# controlshield.net
KiCad netlist of a schematic drawn in EAGLE
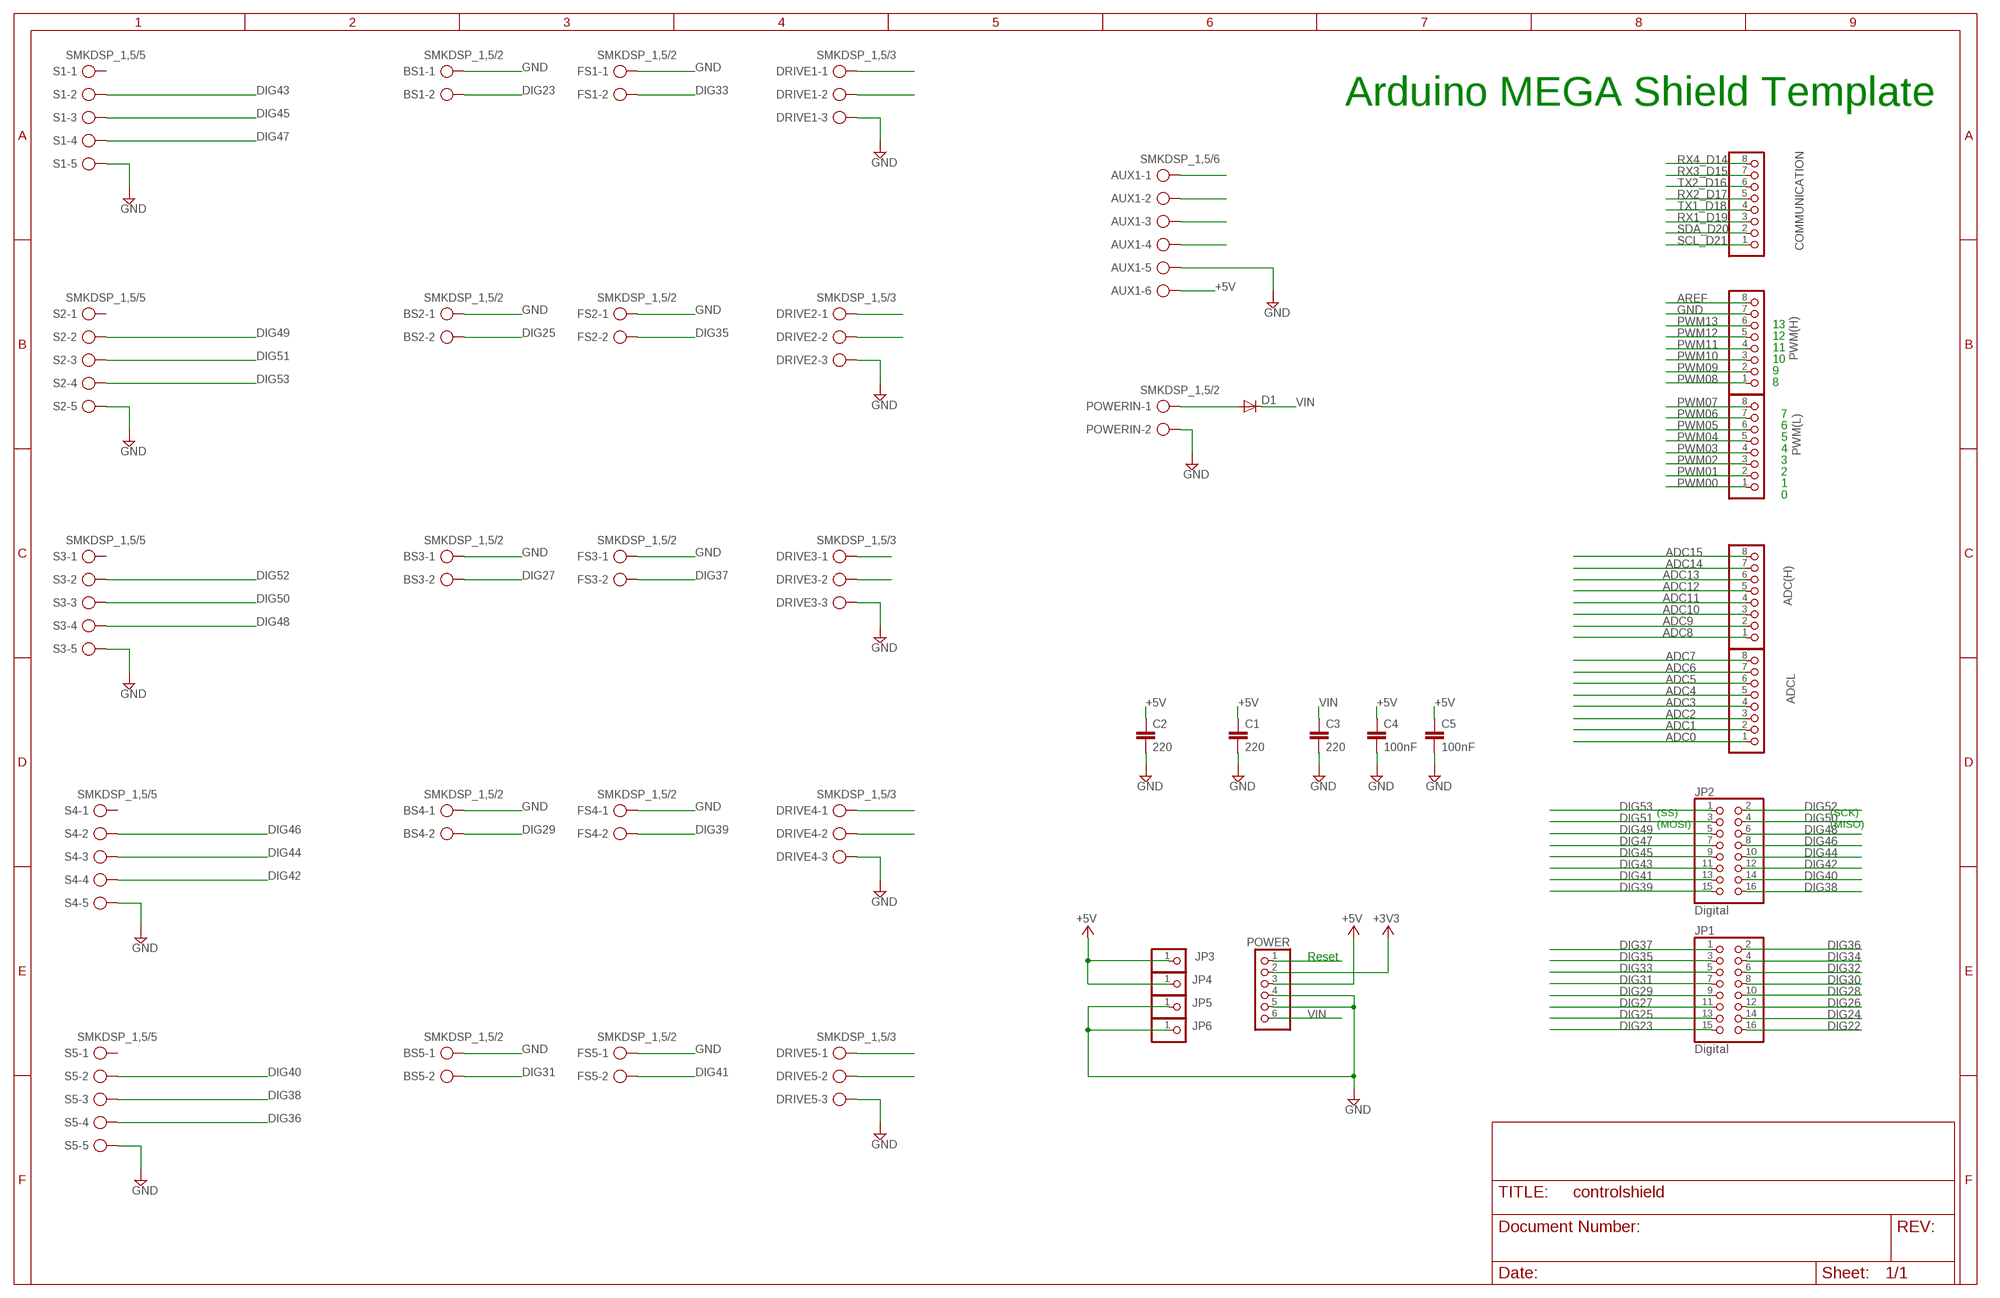
[diagram p0: schematic, sheet 1]

(export (version "E")
  (design (tool "Eeschema 10.0.6"))
  (components
    (comp (ref "ADC(H)")
      (value "PINHD-1X8")
      (footprint "eagle-import:1X08")
      (libsource (lib "eagle-import") (part "PINHD-1X8"))
    )
    (comp (ref "ADCL")
      (value "PINHD-1X8")
      (footprint "eagle-import:1X08")
      (libsource (lib "eagle-import") (part "PINHD-1X8"))
    )
    (comp (ref "AUX1")
      (value "SMKDSP_1,5/6")
      (footprint "eagle-import:SMKDSP_1,5_6")
      (fields (field (name "MF") "FARNELL") (field (name "MPN") "1733619"))
      (libsource (lib "eagle-import") (part "SMKDSP_1,5/6"))
    )
    (comp (ref "BS1")
      (value "SMKDSP_1,5/2")
      (footprint "eagle-import:SMKDSP_1,5_2")
      (fields (field (name "MF") "FARNELL") (field (name "MPN") "1733570"))
      (libsource (lib "eagle-import") (part "SMKDSP_1,5/2"))
    )
    (comp (ref "BS2")
      (value "SMKDSP_1,5/2")
      (footprint "eagle-import:SMKDSP_1,5_2")
      (fields (field (name "MF") "FARNELL") (field (name "MPN") "1733570"))
      (libsource (lib "eagle-import") (part "SMKDSP_1,5/2"))
    )
    (comp (ref "BS3")
      (value "SMKDSP_1,5/2")
      (footprint "eagle-import:SMKDSP_1,5_2")
      (fields (field (name "MF") "FARNELL") (field (name "MPN") "1733570"))
      (libsource (lib "eagle-import") (part "SMKDSP_1,5/2"))
    )
    (comp (ref "BS4")
      (value "SMKDSP_1,5/2")
      (footprint "eagle-import:SMKDSP_1,5_2")
      (fields (field (name "MF") "FARNELL") (field (name "MPN") "1733570"))
      (libsource (lib "eagle-import") (part "SMKDSP_1,5/2"))
    )
    (comp (ref "BS5")
      (value "SMKDSP_1,5/2")
      (footprint "eagle-import:SMKDSP_1,5_2")
      (fields (field (name "MF") "FARNELL") (field (name "MPN") "1733570"))
      (libsource (lib "eagle-import") (part "SMKDSP_1,5/2"))
    )
    (comp (ref "C1")
      (value "220")
      (footprint "eagle-import:C050-075X075")
      (libsource (lib "eagle-import") (part "C-EU050-075X075"))
    )
    (comp (ref "C2")
      (value "220")
      (footprint "eagle-import:C050-075X075")
      (libsource (lib "eagle-import") (part "C-EU050-075X075"))
    )
    (comp (ref "C3")
      (value "220")
      (footprint "eagle-import:C050-075X075")
      (libsource (lib "eagle-import") (part "C-EU050-075X075"))
    )
    (comp (ref "C4")
      (value "100nF")
      (footprint "eagle-import:CAP-PTH-5MM")
      (libsource (lib "eagle-import") (part "CAPPTH1"))
    )
    (comp (ref "C5")
      (value "100nF")
      (footprint "eagle-import:CAP-PTH-5MM")
      (libsource (lib "eagle-import") (part "CAPPTH1"))
    )
    (comp (ref "COMMUNICATION")
      (value "PINHD-1X8")
      (footprint "eagle-import:1X08")
      (libsource (lib "eagle-import") (part "PINHD-1X8"))
    )
    (comp (ref "D1")
      (value "DIODE-DO201-15")
      (footprint "eagle-import:DO201-15")
      (libsource (lib "eagle-import") (part "DIODE-DO201-15"))
    )
    (comp (ref "DRIVE1")
      (value "SMKDSP_1,5/3")
      (footprint "eagle-import:SMKDSP_1,5_3")
      (fields (field (name "MF") "FARNELL") (field (name "MPN") "1733583"))
      (libsource (lib "eagle-import") (part "SMKDSP_1,5/3"))
    )
    (comp (ref "DRIVE2")
      (value "SMKDSP_1,5/3")
      (footprint "eagle-import:SMKDSP_1,5_3")
      (fields (field (name "MF") "FARNELL") (field (name "MPN") "1733583"))
      (libsource (lib "eagle-import") (part "SMKDSP_1,5/3"))
    )
    (comp (ref "DRIVE3")
      (value "SMKDSP_1,5/3")
      (footprint "eagle-import:SMKDSP_1,5_3")
      (fields (field (name "MF") "FARNELL") (field (name "MPN") "1733583"))
      (libsource (lib "eagle-import") (part "SMKDSP_1,5/3"))
    )
    (comp (ref "DRIVE4")
      (value "SMKDSP_1,5/3")
      (footprint "eagle-import:SMKDSP_1,5_3")
      (fields (field (name "MF") "FARNELL") (field (name "MPN") "1733583"))
      (libsource (lib "eagle-import") (part "SMKDSP_1,5/3"))
    )
    (comp (ref "DRIVE5")
      (value "SMKDSP_1,5/3")
      (footprint "eagle-import:SMKDSP_1,5_3")
      (fields (field (name "MF") "FARNELL") (field (name "MPN") "1733583"))
      (libsource (lib "eagle-import") (part "SMKDSP_1,5/3"))
    )
    (comp (ref "FS1")
      (value "SMKDSP_1,5/2")
      (footprint "eagle-import:SMKDSP_1,5_2")
      (fields (field (name "MF") "FARNELL") (field (name "MPN") "1733570"))
      (libsource (lib "eagle-import") (part "SMKDSP_1,5/2"))
    )
    (comp (ref "FS2")
      (value "SMKDSP_1,5/2")
      (footprint "eagle-import:SMKDSP_1,5_2")
      (fields (field (name "MF") "FARNELL") (field (name "MPN") "1733570"))
      (libsource (lib "eagle-import") (part "SMKDSP_1,5/2"))
    )
    (comp (ref "FS3")
      (value "SMKDSP_1,5/2")
      (footprint "eagle-import:SMKDSP_1,5_2")
      (fields (field (name "MF") "FARNELL") (field (name "MPN") "1733570"))
      (libsource (lib "eagle-import") (part "SMKDSP_1,5/2"))
    )
    (comp (ref "FS4")
      (value "SMKDSP_1,5/2")
      (footprint "eagle-import:SMKDSP_1,5_2")
      (fields (field (name "MF") "FARNELL") (field (name "MPN") "1733570"))
      (libsource (lib "eagle-import") (part "SMKDSP_1,5/2"))
    )
    (comp (ref "FS5")
      (value "SMKDSP_1,5/2")
      (footprint "eagle-import:SMKDSP_1,5_2")
      (fields (field (name "MF") "FARNELL") (field (name "MPN") "1733570"))
      (libsource (lib "eagle-import") (part "SMKDSP_1,5/2"))
    )
    (comp (ref "JP1")
      (value "Digital")
      (footprint "eagle-import:2X08")
      (libsource (lib "eagle-import") (part "PINHD-2X8"))
    )
    (comp (ref "JP2")
      (value "Digital")
      (footprint "eagle-import:2X08")
      (libsource (lib "eagle-import") (part "PINHD-2X8"))
    )
    (comp (ref "JP3")
      (value "PINHD-1X1")
      (footprint "eagle-import:1X01")
      (libsource (lib "eagle-import") (part "PINHD-1X1"))
    )
    (comp (ref "JP4")
      (value "PINHD-1X1")
      (footprint "eagle-import:1X01")
      (libsource (lib "eagle-import") (part "PINHD-1X1"))
    )
    (comp (ref "JP5")
      (value "PINHD-1X1")
      (footprint "eagle-import:1X01")
      (libsource (lib "eagle-import") (part "PINHD-1X1"))
    )
    (comp (ref "JP6")
      (value "PINHD-1X1")
      (footprint "eagle-import:1X01")
      (libsource (lib "eagle-import") (part "PINHD-1X1"))
    )
    (comp (ref "POWER")
      (value "PINHD-1X6")
      (footprint "eagle-import:1X06")
      (libsource (lib "eagle-import") (part "PINHD-1X6"))
    )
    (comp (ref "POWERIN")
      (value "SMKDSP_1,5/2")
      (footprint "eagle-import:SMKDSP_1,5_2")
      (fields (field (name "MF") "FARNELL") (field (name "MPN") "1733570"))
      (libsource (lib "eagle-import") (part "SMKDSP_1,5/2"))
    )
    (comp (ref "PWM(H)")
      (value "PINHD-1X8")
      (footprint "eagle-import:1X08")
      (libsource (lib "eagle-import") (part "PINHD-1X8"))
    )
    (comp (ref "PWM(L)")
      (value "PINHD-1X8")
      (footprint "eagle-import:1X08")
      (libsource (lib "eagle-import") (part "PINHD-1X8"))
    )
    (comp (ref "S1")
      (value "SMKDSP_1,5/5")
      (footprint "eagle-import:SMKDSP_1,5_5")
      (libsource (lib "eagle-import") (part "SMKDSP_1,5/5"))
    )
    (comp (ref "S2")
      (value "SMKDSP_1,5/5")
      (footprint "eagle-import:SMKDSP_1,5_5")
      (libsource (lib "eagle-import") (part "SMKDSP_1,5/5"))
    )
    (comp (ref "S3")
      (value "SMKDSP_1,5/5")
      (footprint "eagle-import:SMKDSP_1,5_5")
      (libsource (lib "eagle-import") (part "SMKDSP_1,5/5"))
    )
    (comp (ref "S4")
      (value "SMKDSP_1,5/5")
      (footprint "eagle-import:SMKDSP_1,5_5")
      (libsource (lib "eagle-import") (part "SMKDSP_1,5/5"))
    )
    (comp (ref "S5")
      (value "SMKDSP_1,5/5")
      (footprint "eagle-import:SMKDSP_1,5_5")
      (libsource (lib "eagle-import") (part "SMKDSP_1,5/5"))
    )
  )
  (nets
    (net (code "1") (name "+3V3") (class "Default")
      (node (ref "POWER") (pin "2") (pinfunction "2_2") (pintype "passive"))
    )
    (net (code "2") (name "+5V") (class "Default")
      (node (ref "AUX1") (pin "6") (pinfunction "KL_6") (pintype "passive"))
      (node (ref "C1") (pin "1") (pinfunction "1_1") (pintype "passive"))
      (node (ref "C2") (pin "1") (pinfunction "1_1") (pintype "passive"))
      (node (ref "C4") (pin "1") (pinfunction "1_1") (pintype "passive"))
      (node (ref "C5") (pin "1") (pinfunction "1_1") (pintype "passive"))
      (node (ref "JP3") (pin "1") (pinfunction "1_1") (pintype "passive"))
      (node (ref "JP4") (pin "1") (pinfunction "1_1") (pintype "passive"))
      (node (ref "POWER") (pin "3") (pinfunction "3_3") (pintype "passive"))
    )
    (net (code "3") (name "/ADC0") (class "Default")
      (node (ref "ADCL") (pin "1") (pinfunction "1_1") (pintype "passive"))
    )
    (net (code "4") (name "/ADC1") (class "Default")
      (node (ref "ADCL") (pin "2") (pinfunction "2_2") (pintype "passive"))
    )
    (net (code "5") (name "/ADC2") (class "Default")
      (node (ref "ADCL") (pin "3") (pinfunction "3_3") (pintype "passive"))
    )
    (net (code "6") (name "/ADC3") (class "Default")
      (node (ref "ADCL") (pin "4") (pinfunction "4_4") (pintype "passive"))
    )
    (net (code "7") (name "/ADC4") (class "Default")
      (node (ref "ADCL") (pin "5") (pinfunction "5_5") (pintype "passive"))
    )
    (net (code "8") (name "/ADC5") (class "Default")
      (node (ref "ADCL") (pin "6") (pinfunction "6_6") (pintype "passive"))
    )
    (net (code "9") (name "/ADC6") (class "Default")
      (node (ref "ADCL") (pin "7") (pinfunction "7_7") (pintype "passive"))
    )
    (net (code "10") (name "/ADC7") (class "Default")
      (node (ref "ADCL") (pin "8") (pinfunction "8_8") (pintype "passive"))
    )
    (net (code "11") (name "/ADC8") (class "Default")
      (node (ref "ADC(H)") (pin "1") (pinfunction "1_1") (pintype "passive"))
    )
    (net (code "12") (name "/ADC9") (class "Default")
      (node (ref "ADC(H)") (pin "2") (pinfunction "2_2") (pintype "passive"))
    )
    (net (code "13") (name "/ADC10") (class "Default")
      (node (ref "ADC(H)") (pin "3") (pinfunction "3_3") (pintype "passive"))
    )
    (net (code "14") (name "/ADC11") (class "Default")
      (node (ref "ADC(H)") (pin "4") (pinfunction "4_4") (pintype "passive"))
    )
    (net (code "15") (name "/ADC12") (class "Default")
      (node (ref "ADC(H)") (pin "5") (pinfunction "5_5") (pintype "passive"))
    )
    (net (code "16") (name "/ADC13") (class "Default")
      (node (ref "ADC(H)") (pin "6") (pinfunction "6_6") (pintype "passive"))
    )
    (net (code "17") (name "/ADC14") (class "Default")
      (node (ref "ADC(H)") (pin "7") (pinfunction "7_7") (pintype "passive"))
    )
    (net (code "18") (name "/ADC15") (class "Default")
      (node (ref "ADC(H)") (pin "8") (pinfunction "8_8") (pintype "passive"))
    )
    (net (code "19") (name "/AREF") (class "Default")
      (node (ref "PWM(H)") (pin "8") (pinfunction "8_8") (pintype "passive"))
    )
    (net (code "20") (name "/DIG22") (class "Default")
      (node (ref "DRIVE1") (pin "1") (pinfunction "KL_1") (pintype "passive"))
      (node (ref "JP1") (pin "16") (pinfunction "16_16") (pintype "passive"))
    )
    (net (code "21") (name "/DIG23") (class "Default")
      (node (ref "BS1") (pin "2") (pinfunction "KL_2") (pintype "passive"))
      (node (ref "JP1") (pin "15") (pinfunction "15_15") (pintype "passive"))
    )
    (net (code "22") (name "/DIG24") (class "Default")
      (node (ref "DRIVE1") (pin "2") (pinfunction "KL_2") (pintype "passive"))
      (node (ref "JP1") (pin "14") (pinfunction "14_14") (pintype "passive"))
    )
    (net (code "23") (name "/DIG25") (class "Default")
      (node (ref "BS2") (pin "2") (pinfunction "KL_2") (pintype "passive"))
      (node (ref "JP1") (pin "13") (pinfunction "13_13") (pintype "passive"))
    )
    (net (code "24") (name "/DIG26") (class "Default")
      (node (ref "DRIVE2") (pin "1") (pinfunction "KL_1") (pintype "passive"))
      (node (ref "JP1") (pin "12") (pinfunction "12_12") (pintype "passive"))
    )
    (net (code "25") (name "/DIG27") (class "Default")
      (node (ref "BS3") (pin "2") (pinfunction "KL_2") (pintype "passive"))
      (node (ref "JP1") (pin "11") (pinfunction "11_11") (pintype "passive"))
    )
    (net (code "26") (name "/DIG28") (class "Default")
      (node (ref "DRIVE2") (pin "2") (pinfunction "KL_2") (pintype "passive"))
      (node (ref "JP1") (pin "10") (pinfunction "10_10") (pintype "passive"))
    )
    (net (code "27") (name "/DIG29") (class "Default")
      (node (ref "BS4") (pin "2") (pinfunction "KL_2") (pintype "passive"))
      (node (ref "JP1") (pin "9") (pinfunction "9_9") (pintype "passive"))
    )
    (net (code "28") (name "/DIG30") (class "Default")
      (node (ref "JP1") (pin "8") (pinfunction "8_8") (pintype "passive"))
    )
    (net (code "29") (name "/DIG31") (class "Default")
      (node (ref "BS5") (pin "2") (pinfunction "KL_2") (pintype "passive"))
      (node (ref "JP1") (pin "7") (pinfunction "7_7") (pintype "passive"))
    )
    (net (code "30") (name "/DIG32") (class "Default")
      (node (ref "JP1") (pin "6") (pinfunction "6_6") (pintype "passive"))
    )
    (net (code "31") (name "/DIG33") (class "Default")
      (node (ref "FS1") (pin "2") (pinfunction "KL_2") (pintype "passive"))
      (node (ref "JP1") (pin "5") (pinfunction "5_5") (pintype "passive"))
    )
    (net (code "32") (name "/DIG34") (class "Default")
      (node (ref "JP1") (pin "4") (pinfunction "4_4") (pintype "passive"))
    )
    (net (code "33") (name "/DIG35") (class "Default")
      (node (ref "FS2") (pin "2") (pinfunction "KL_2") (pintype "passive"))
      (node (ref "JP1") (pin "3") (pinfunction "3_3") (pintype "passive"))
    )
    (net (code "34") (name "/DIG36") (class "Default")
      (node (ref "JP1") (pin "2") (pinfunction "2_2") (pintype "passive"))
      (node (ref "S5") (pin "4") (pinfunction "KL_4") (pintype "passive"))
    )
    (net (code "35") (name "/DIG37") (class "Default")
      (node (ref "FS3") (pin "2") (pinfunction "KL_2") (pintype "passive"))
      (node (ref "JP1") (pin "1") (pinfunction "1_1") (pintype "passive"))
    )
    (net (code "36") (name "/DIG38") (class "Default")
      (node (ref "JP2") (pin "16") (pinfunction "16_16") (pintype "passive"))
      (node (ref "S5") (pin "3") (pinfunction "KL_3") (pintype "passive"))
    )
    (net (code "37") (name "/DIG39") (class "Default")
      (node (ref "FS4") (pin "2") (pinfunction "KL_2") (pintype "passive"))
      (node (ref "JP2") (pin "15") (pinfunction "15_15") (pintype "passive"))
    )
    (net (code "38") (name "/DIG40") (class "Default")
      (node (ref "JP2") (pin "14") (pinfunction "14_14") (pintype "passive"))
      (node (ref "S5") (pin "2") (pinfunction "KL_2") (pintype "passive"))
    )
    (net (code "39") (name "/DIG41") (class "Default")
      (node (ref "FS5") (pin "2") (pinfunction "KL_2") (pintype "passive"))
      (node (ref "JP2") (pin "13") (pinfunction "13_13") (pintype "passive"))
    )
    (net (code "40") (name "/DIG42") (class "Default")
      (node (ref "JP2") (pin "12") (pinfunction "12_12") (pintype "passive"))
      (node (ref "S4") (pin "4") (pinfunction "KL_4") (pintype "passive"))
    )
    (net (code "41") (name "/DIG43") (class "Default")
      (node (ref "JP2") (pin "11") (pinfunction "11_11") (pintype "passive"))
      (node (ref "S1") (pin "2") (pinfunction "KL_2") (pintype "passive"))
    )
    (net (code "42") (name "/DIG44") (class "Default")
      (node (ref "JP2") (pin "10") (pinfunction "10_10") (pintype "passive"))
      (node (ref "S4") (pin "3") (pinfunction "KL_3") (pintype "passive"))
    )
    (net (code "43") (name "/DIG45") (class "Default")
      (node (ref "JP2") (pin "9") (pinfunction "9_9") (pintype "passive"))
      (node (ref "S1") (pin "3") (pinfunction "KL_3") (pintype "passive"))
    )
    (net (code "44") (name "/DIG46") (class "Default")
      (node (ref "JP2") (pin "8") (pinfunction "8_8") (pintype "passive"))
      (node (ref "S4") (pin "2") (pinfunction "KL_2") (pintype "passive"))
    )
    (net (code "45") (name "/DIG47") (class "Default")
      (node (ref "JP2") (pin "7") (pinfunction "7_7") (pintype "passive"))
      (node (ref "S1") (pin "4") (pinfunction "KL_4") (pintype "passive"))
    )
    (net (code "46") (name "/DIG48") (class "Default")
      (node (ref "JP2") (pin "6") (pinfunction "6_6") (pintype "passive"))
      (node (ref "S3") (pin "4") (pinfunction "KL_4") (pintype "passive"))
    )
    (net (code "47") (name "/DIG49") (class "Default")
      (node (ref "JP2") (pin "5") (pinfunction "5_5") (pintype "passive"))
      (node (ref "S2") (pin "2") (pinfunction "KL_2") (pintype "passive"))
    )
    (net (code "48") (name "/DIG50") (class "Default")
      (node (ref "JP2") (pin "4") (pinfunction "4_4") (pintype "passive"))
      (node (ref "S3") (pin "3") (pinfunction "KL_3") (pintype "passive"))
    )
    (net (code "49") (name "/DIG51") (class "Default")
      (node (ref "JP2") (pin "3") (pinfunction "3_3") (pintype "passive"))
      (node (ref "S2") (pin "3") (pinfunction "KL_3") (pintype "passive"))
    )
    (net (code "50") (name "/DIG52") (class "Default")
      (node (ref "JP2") (pin "2") (pinfunction "2_2") (pintype "passive"))
      (node (ref "S3") (pin "2") (pinfunction "KL_2") (pintype "passive"))
    )
    (net (code "51") (name "/DIG53") (class "Default")
      (node (ref "JP2") (pin "1") (pinfunction "1_1") (pintype "passive"))
      (node (ref "S2") (pin "4") (pinfunction "KL_4") (pintype "passive"))
    )
    (net (code "52") (name "/PWM00") (class "Default")
      (node (ref "PWM(L)") (pin "1") (pinfunction "1_1") (pintype "passive"))
    )
    (net (code "53") (name "/PWM01") (class "Default")
      (node (ref "PWM(L)") (pin "2") (pinfunction "2_2") (pintype "passive"))
    )
    (net (code "54") (name "/PWM02") (class "Default")
      (node (ref "PWM(L)") (pin "3") (pinfunction "3_3") (pintype "passive"))
    )
    (net (code "55") (name "/PWM03") (class "Default")
      (node (ref "DRIVE3") (pin "1") (pinfunction "KL_1") (pintype "passive"))
      (node (ref "PWM(L)") (pin "4") (pinfunction "4_4") (pintype "passive"))
    )
    (net (code "56") (name "/PWM04") (class "Default")
      (node (ref "DRIVE3") (pin "2") (pinfunction "KL_2") (pintype "passive"))
      (node (ref "PWM(L)") (pin "5") (pinfunction "5_5") (pintype "passive"))
    )
    (net (code "57") (name "/PWM05") (class "Default")
      (node (ref "DRIVE4") (pin "1") (pinfunction "KL_1") (pintype "passive"))
      (node (ref "PWM(L)") (pin "6") (pinfunction "6_6") (pintype "passive"))
    )
    (net (code "58") (name "/PWM06") (class "Default")
      (node (ref "DRIVE4") (pin "2") (pinfunction "KL_2") (pintype "passive"))
      (node (ref "PWM(L)") (pin "7") (pinfunction "7_7") (pintype "passive"))
    )
    (net (code "59") (name "/PWM07") (class "Default")
      (node (ref "DRIVE5") (pin "1") (pinfunction "KL_1") (pintype "passive"))
      (node (ref "PWM(L)") (pin "8") (pinfunction "8_8") (pintype "passive"))
    )
    (net (code "60") (name "/PWM08") (class "Default")
      (node (ref "DRIVE5") (pin "2") (pinfunction "KL_2") (pintype "passive"))
      (node (ref "PWM(H)") (pin "1") (pinfunction "1_1") (pintype "passive"))
    )
    (net (code "61") (name "/PWM09") (class "Default")
      (node (ref "AUX1") (pin "1") (pinfunction "KL_1") (pintype "passive"))
      (node (ref "PWM(H)") (pin "2") (pinfunction "2_2") (pintype "passive"))
    )
    (net (code "62") (name "/PWM10") (class "Default")
      (node (ref "AUX1") (pin "2") (pinfunction "KL_2") (pintype "passive"))
      (node (ref "PWM(H)") (pin "3") (pinfunction "3_3") (pintype "passive"))
    )
    (net (code "63") (name "/PWM11") (class "Default")
      (node (ref "AUX1") (pin "3") (pinfunction "KL_3") (pintype "passive"))
      (node (ref "PWM(H)") (pin "4") (pinfunction "4_4") (pintype "passive"))
    )
    (net (code "64") (name "/PWM12") (class "Default")
      (node (ref "AUX1") (pin "4") (pinfunction "KL_4") (pintype "passive"))
      (node (ref "PWM(H)") (pin "5") (pinfunction "5_5") (pintype "passive"))
    )
    (net (code "65") (name "/PWM13") (class "Default")
      (node (ref "PWM(H)") (pin "6") (pinfunction "6_6") (pintype "passive"))
    )
    (net (code "66") (name "/RX1_D19") (class "Default")
      (node (ref "COMMUNICATION") (pin "3") (pinfunction "3_3") (pintype "passive"))
    )
    (net (code "67") (name "/RX2_D17") (class "Default")
      (node (ref "COMMUNICATION") (pin "5") (pinfunction "5_5") (pintype "passive"))
    )
    (net (code "68") (name "/RX3_D15") (class "Default")
      (node (ref "COMMUNICATION") (pin "7") (pinfunction "7_7") (pintype "passive"))
    )
    (net (code "69") (name "/RX4_D14") (class "Default")
      (node (ref "COMMUNICATION") (pin "8") (pinfunction "8_8") (pintype "passive"))
    )
    (net (code "70") (name "/SCL_D21") (class "Default")
      (node (ref "COMMUNICATION") (pin "1") (pinfunction "1_1") (pintype "passive"))
    )
    (net (code "71") (name "/SDA_D20") (class "Default")
      (node (ref "COMMUNICATION") (pin "2") (pinfunction "2_2") (pintype "passive"))
    )
    (net (code "72") (name "/TX1_D18") (class "Default")
      (node (ref "COMMUNICATION") (pin "4") (pinfunction "4_4") (pintype "passive"))
    )
    (net (code "73") (name "/TX2_D16") (class "Default")
      (node (ref "COMMUNICATION") (pin "6") (pinfunction "6_6") (pintype "passive"))
    )
    (net (code "74") (name "/VIN") (class "Default")
      (node (ref "C3") (pin "1") (pinfunction "1_1") (pintype "passive"))
      (node (ref "D1") (pin "C") (pinfunction "C_C") (pintype "passive"))
      (node (ref "POWER") (pin "6") (pinfunction "6_6") (pintype "passive"))
    )
    (net (code "75") (name "GND") (class "Default")
      (node (ref "AUX1") (pin "5") (pinfunction "KL_5") (pintype "passive"))
      (node (ref "BS1") (pin "1") (pinfunction "KL_1") (pintype "passive"))
      (node (ref "BS2") (pin "1") (pinfunction "KL_1") (pintype "passive"))
      (node (ref "BS3") (pin "1") (pinfunction "KL_1") (pintype "passive"))
      (node (ref "BS4") (pin "1") (pinfunction "KL_1") (pintype "passive"))
      (node (ref "BS5") (pin "1") (pinfunction "KL_1") (pintype "passive"))
      (node (ref "C1") (pin "2") (pinfunction "2_2") (pintype "passive"))
      (node (ref "C2") (pin "2") (pinfunction "2_2") (pintype "passive"))
      (node (ref "C3") (pin "2") (pinfunction "2_2") (pintype "passive"))
      (node (ref "C4") (pin "2") (pinfunction "2_2") (pintype "passive"))
      (node (ref "C5") (pin "2") (pinfunction "2_2") (pintype "passive"))
      (node (ref "DRIVE1") (pin "3") (pinfunction "KL_3") (pintype "passive"))
      (node (ref "DRIVE2") (pin "3") (pinfunction "KL_3") (pintype "passive"))
      (node (ref "DRIVE3") (pin "3") (pinfunction "KL_3") (pintype "passive"))
      (node (ref "DRIVE4") (pin "3") (pinfunction "KL_3") (pintype "passive"))
      (node (ref "DRIVE5") (pin "3") (pinfunction "KL_3") (pintype "passive"))
      (node (ref "FS1") (pin "1") (pinfunction "KL_1") (pintype "passive"))
      (node (ref "FS2") (pin "1") (pinfunction "KL_1") (pintype "passive"))
      (node (ref "FS3") (pin "1") (pinfunction "KL_1") (pintype "passive"))
      (node (ref "FS4") (pin "1") (pinfunction "KL_1") (pintype "passive"))
      (node (ref "FS5") (pin "1") (pinfunction "KL_1") (pintype "passive"))
      (node (ref "JP5") (pin "1") (pinfunction "1_1") (pintype "passive"))
      (node (ref "JP6") (pin "1") (pinfunction "1_1") (pintype "passive"))
      (node (ref "POWER") (pin "4") (pinfunction "4_4") (pintype "passive"))
      (node (ref "POWER") (pin "5") (pinfunction "5_5") (pintype "passive"))
      (node (ref "POWERIN") (pin "2") (pinfunction "KL_2") (pintype "passive"))
      (node (ref "PWM(H)") (pin "7") (pinfunction "7_7") (pintype "passive"))
      (node (ref "S1") (pin "5") (pinfunction "KL_5") (pintype "passive"))
      (node (ref "S2") (pin "5") (pinfunction "KL_5") (pintype "passive"))
      (node (ref "S3") (pin "5") (pinfunction "KL_5") (pintype "passive"))
      (node (ref "S4") (pin "5") (pinfunction "KL_5") (pintype "passive"))
      (node (ref "S5") (pin "5") (pinfunction "KL_5") (pintype "passive"))
    )
    (net (code "76") (name "Net-(POWERINA-KL)") (class "Default")
      (node (ref "D1") (pin "A") (pinfunction "A_A") (pintype "passive"))
      (node (ref "POWERIN") (pin "1") (pinfunction "KL_1") (pintype "passive"))
    )
    (net (code "77") (name "unconnected-(POWER-Pad1)") (class "Default")
      (node (ref "POWER") (pin "1") (pinfunction "1_1") (pintype "passive"))
    )
    (net (code "78") (name "unconnected-(S1A-KL-Pad1)") (class "Default")
      (node (ref "S1") (pin "1") (pinfunction "KL_1") (pintype "passive"))
    )
    (net (code "79") (name "unconnected-(S2A-KL-Pad1)") (class "Default")
      (node (ref "S2") (pin "1") (pinfunction "KL_1") (pintype "passive"))
    )
    (net (code "80") (name "unconnected-(S3A-KL-Pad1)") (class "Default")
      (node (ref "S3") (pin "1") (pinfunction "KL_1") (pintype "passive"))
    )
    (net (code "81") (name "unconnected-(S4A-KL-Pad1)") (class "Default")
      (node (ref "S4") (pin "1") (pinfunction "KL_1") (pintype "passive"))
    )
    (net (code "82") (name "unconnected-(S5A-KL-Pad1)") (class "Default")
      (node (ref "S5") (pin "1") (pinfunction "KL_1") (pintype "passive"))
    )
  )
)
